# DISPLAY.net
KiCad netlist of a schematic drawn in Altium Designer
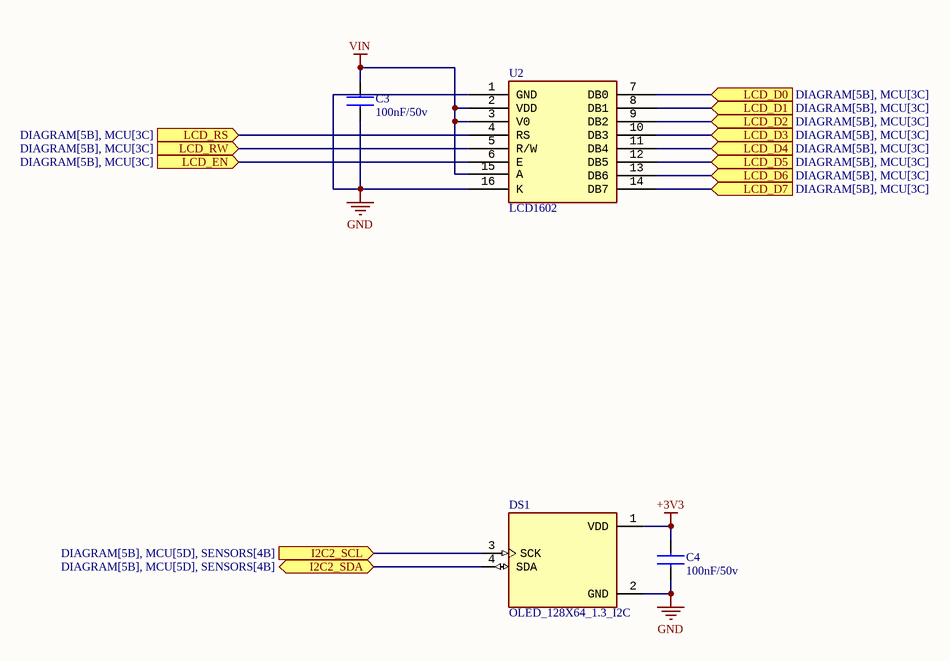
[diagram p0: DISPLAY.SchDoc]

(export (version "E")
  (design (tool "Eeschema 10.0.6"))
  (components
    (comp (ref "C3") (value "100nF/50v") (footprint "CAP-CER-0805") (libsource (lib "ID") (part "CAP-CER")))
    (comp (ref "C4") (value "100nF/50v") (footprint "CAP-CER-0805") (libsource (lib "ID") (part "CAP-CER")))
    (comp (ref "DS1")
      (value "OLED_128X64_1.3_I2C")
      (footprint "LCD_OLED_128X64_1.3_I2C")
      (fields
        (field (name "MF") "UNIVERSAL-SOLDER Electronics Ltd")
        (field (name "MP") "OLED 128x64 1.3&quot; I2C")
        (field (name "MFR# #") "OLED_128X64_1.3_I2C")
      )
      (libsource (lib "Database_Libs1") (part "OLED_128X64_1.3_I2C"))
    )
    (comp (ref "U2") (value "LCD1602") (footprint "LCD16X2") (libsource (lib "ID") (part "LCD1602")))
  )
  (nets
    (net (code "1") (name "+3V3") (class "Default")
      (node (ref "C4") (pin "2") (pinfunction "2_2") (pintype "passive"))
      (node (ref "DS1") (pin "1") (pinfunction "VDD_1") (pintype "power_in"))
    )
    (net (code "2") (name "/I2C2_SCL") (class "Default")
      (node (ref "DS1") (pin "3") (pinfunction "SCK_3") (pintype "input"))
    )
    (net (code "3") (name "/I2C2_SDA") (class "Default")
      (node (ref "DS1") (pin "4") (pinfunction "SDA_4") (pintype "bidirectional"))
    )
    (net (code "4") (name "/LCD_D0") (class "Default")
      (node (ref "U2") (pin "7") (pinfunction "DB0_7") (pintype "passive"))
    )
    (net (code "5") (name "/LCD_D1") (class "Default")
      (node (ref "U2") (pin "8") (pinfunction "DB1_8") (pintype "passive"))
    )
    (net (code "6") (name "/LCD_D2") (class "Default")
      (node (ref "U2") (pin "9") (pinfunction "DB2_9") (pintype "passive"))
    )
    (net (code "7") (name "/LCD_D3") (class "Default")
      (node (ref "U2") (pin "10") (pinfunction "DB3_10") (pintype "passive"))
    )
    (net (code "8") (name "/LCD_D4") (class "Default")
      (node (ref "U2") (pin "11") (pinfunction "DB4_11") (pintype "passive"))
    )
    (net (code "9") (name "/LCD_D5") (class "Default")
      (node (ref "U2") (pin "12") (pinfunction "DB5_12") (pintype "passive"))
    )
    (net (code "10") (name "/LCD_D6") (class "Default")
      (node (ref "U2") (pin "13") (pinfunction "DB6_13") (pintype "passive"))
    )
    (net (code "11") (name "/LCD_D7") (class "Default")
      (node (ref "U2") (pin "14") (pinfunction "DB7_14") (pintype "passive"))
    )
    (net (code "12") (name "/LCD_EN") (class "Default")
      (node (ref "U2") (pin "6") (pinfunction "E_6") (pintype "passive"))
    )
    (net (code "13") (name "/LCD_RS") (class "Default")
      (node (ref "U2") (pin "4") (pinfunction "RS_4") (pintype "passive"))
    )
    (net (code "14") (name "/LCD_RW") (class "Default")
      (node (ref "U2") (pin "5") (pinfunction "R/W_5") (pintype "passive"))
    )
    (net (code "15") (name "GND") (class "Default")
      (node (ref "C3") (pin "1") (pinfunction "1_1") (pintype "passive"))
      (node (ref "C4") (pin "1") (pinfunction "1_1") (pintype "passive"))
      (node (ref "DS1") (pin "2") (pinfunction "GND_2") (pintype "power_in"))
      (node (ref "U2") (pin "1") (pinfunction "GND_1") (pintype "passive"))
      (node (ref "U2") (pin "16") (pinfunction "K_16") (pintype "passive"))
    )
    (net (code "16") (name "VIN") (class "Default")
      (node (ref "C3") (pin "2") (pinfunction "2_2") (pintype "passive"))
      (node (ref "U2") (pin "15") (pinfunction "A_15") (pintype "passive"))
      (node (ref "U2") (pin "2") (pinfunction "VDD_2") (pintype "passive"))
      (node (ref "U2") (pin "3") (pinfunction "V0_3") (pintype "passive"))
    )
  )
)
